# -46342_21-004_3_3.net
KiCad netlist of a schematic drawn in Altium Designer
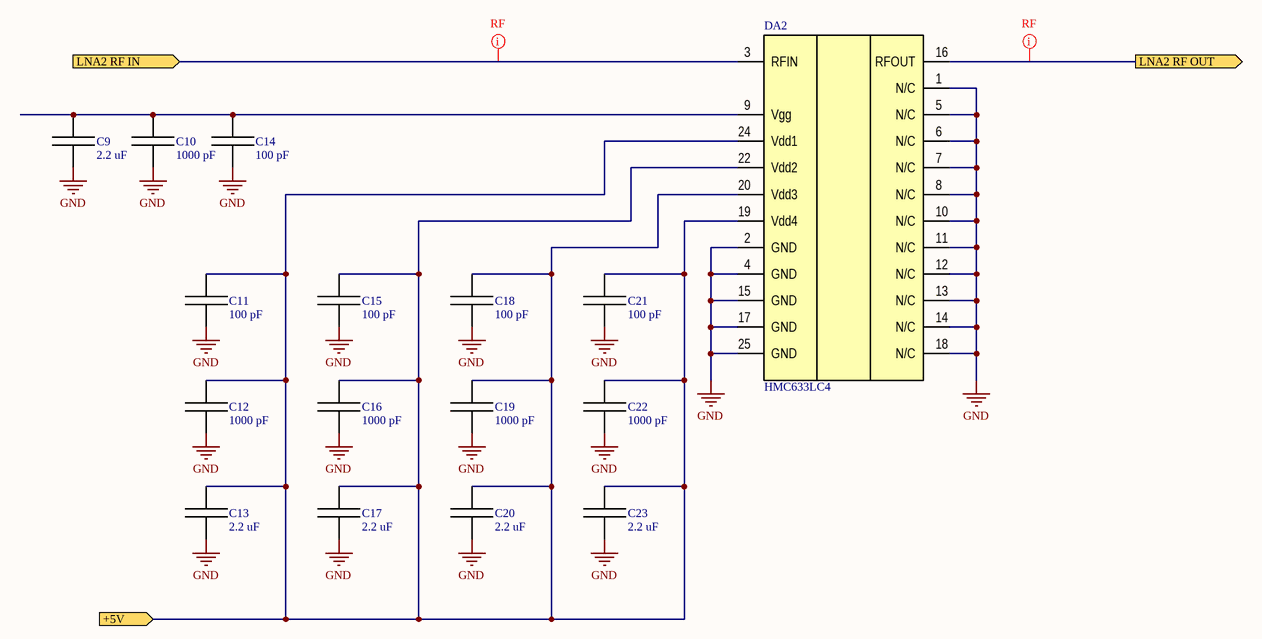
[diagram p0: МПСУ-46342.21-004 Э3 Лист3.SchDoc]

(export (version "E")
  (design (tool "Eeschema 10.0.6"))
  (components
    (comp (ref "C9")
      (value "2.2 uF")
      (footprint "CAPC100X50X55L20N")
      (description "Capacitor, generic")
      (fields (field (name "TOLERANCE") "5 %"))
      (libsource (lib "StudentsLibrary") (part "Capacitor"))
    )
    (comp (ref "C10")
      (value "1000 pF")
      (footprint "CAPC100X50X55L20N")
      (description "Capacitor, generic")
      (fields (field (name "TOLERANCE") "5 %"))
      (libsource (lib "StudentsLibrary") (part "Capacitor"))
    )
    (comp (ref "C11")
      (value "100 pF")
      (footprint "CAPC100X50X55L20N")
      (description "Capacitor, generic")
      (fields (field (name "TOLERANCE") "5 %"))
      (libsource (lib "StudentsLibrary") (part "Capacitor"))
    )
    (comp (ref "C12")
      (value "1000 pF")
      (footprint "CAPC100X50X55L20N")
      (description "Capacitor, generic")
      (fields (field (name "TOLERANCE") "5 %"))
      (libsource (lib "StudentsLibrary") (part "Capacitor"))
    )
    (comp (ref "C13")
      (value "2.2 uF")
      (footprint "CAPC160X80X90L30N")
      (description "Capacitor, generic")
      (fields (field (name "TOLERANCE") "5 %"))
      (libsource (lib "StudentsLibrary") (part "Capacitor"))
    )
    (comp (ref "C14")
      (value "100 pF")
      (footprint "CAPC100X50X55L20N")
      (description "Capacitor, generic")
      (fields (field (name "TOLERANCE") "5 %"))
      (libsource (lib "StudentsLibrary") (part "Capacitor"))
    )
    (comp (ref "C15")
      (value "100 pF")
      (footprint "CAPC100X50X55L20N")
      (description "Capacitor, generic")
      (fields (field (name "TOLERANCE") "5 %"))
      (libsource (lib "StudentsLibrary") (part "Capacitor"))
    )
    (comp (ref "C16")
      (value "1000 pF")
      (footprint "CAPC100X50X55L20N")
      (description "Capacitor, generic")
      (fields (field (name "TOLERANCE") "5 %"))
      (libsource (lib "StudentsLibrary") (part "Capacitor"))
    )
    (comp (ref "C17")
      (value "2.2 uF")
      (footprint "CAPC160X80X90L30N")
      (description "Capacitor, generic")
      (fields (field (name "TOLERANCE") "5 %"))
      (libsource (lib "StudentsLibrary") (part "Capacitor"))
    )
    (comp (ref "C18")
      (value "100 pF")
      (footprint "CAPC100X50X55L20N")
      (description "Capacitor, generic")
      (fields (field (name "TOLERANCE") "5 %"))
      (libsource (lib "StudentsLibrary") (part "Capacitor"))
    )
    (comp (ref "C19")
      (value "1000 pF")
      (footprint "CAPC100X50X55L20N")
      (description "Capacitor, generic")
      (fields (field (name "TOLERANCE") "5 %"))
      (libsource (lib "StudentsLibrary") (part "Capacitor"))
    )
    (comp (ref "C20")
      (value "2.2 uF")
      (footprint "CAPC160X80X90L30N")
      (description "Capacitor, generic")
      (fields (field (name "TOLERANCE") "5 %"))
      (libsource (lib "StudentsLibrary") (part "Capacitor"))
    )
    (comp (ref "C21")
      (value "100 pF")
      (footprint "CAPC100X50X55L20N")
      (description "Capacitor, generic")
      (fields (field (name "TOLERANCE") "5 %"))
      (libsource (lib "StudentsLibrary") (part "Capacitor"))
    )
    (comp (ref "C22")
      (value "1000 pF")
      (footprint "CAPC100X50X55L20N")
      (description "Capacitor, generic")
      (fields (field (name "TOLERANCE") "5 %"))
      (libsource (lib "StudentsLibrary") (part "Capacitor"))
    )
    (comp (ref "C23")
      (value "2.2 uF")
      (footprint "CAPC160X80X90L30N")
      (description "Capacitor, generic")
      (fields (field (name "TOLERANCE") "5 %"))
      (libsource (lib "StudentsLibrary") (part "Capacitor"))
    )
    (comp (ref "DA2")
      (value "HMC633LC4")
      (footprint "PQFN25P50_390X390X100L32X30T250N")
      (description "GaAs, pHEMT MMIC DRIVERAMPLIFIER, 5.5 - 17 GHz")
      (fields (field (name "MANUFACTURER") "Analog Devices"))
      (libsource (lib "receiver") (part "HMC633LC4"))
    )
  )
  (nets
    (net (code "1") (name "/+5V") (class "Default")
      (node (ref "C11") (pin "2") (pinfunction "2_2") (pintype "passive"))
      (node (ref "C12") (pin "2") (pinfunction "2_2") (pintype "passive"))
      (node (ref "C13") (pin "2") (pinfunction "2_2") (pintype "passive"))
      (node (ref "C15") (pin "2") (pinfunction "2_2") (pintype "passive"))
      (node (ref "C16") (pin "2") (pinfunction "2_2") (pintype "passive"))
      (node (ref "C17") (pin "2") (pinfunction "2_2") (pintype "passive"))
      (node (ref "C18") (pin "2") (pinfunction "2_2") (pintype "passive"))
      (node (ref "C19") (pin "2") (pinfunction "2_2") (pintype "passive"))
      (node (ref "C20") (pin "2") (pinfunction "2_2") (pintype "passive"))
      (node (ref "C21") (pin "2") (pinfunction "2_2") (pintype "passive"))
      (node (ref "C22") (pin "2") (pinfunction "2_2") (pintype "passive"))
      (node (ref "C23") (pin "2") (pinfunction "2_2") (pintype "passive"))
      (node (ref "DA2") (pin "19") (pinfunction "Vdd4_19") (pintype "passive"))
      (node (ref "DA2") (pin "20") (pinfunction "Vdd3_20") (pintype "passive"))
      (node (ref "DA2") (pin "22") (pinfunction "Vdd2_22") (pintype "passive"))
      (node (ref "DA2") (pin "24") (pinfunction "Vdd1_24") (pintype "passive"))
    )
    (net (code "2") (name "/LNA2 RF IN") (class "Default")
      (node (ref "DA2") (pin "3") (pinfunction "RFIN_3") (pintype "passive"))
    )
    (net (code "3") (name "/LNA2 RF OUT") (class "Default")
      (node (ref "DA2") (pin "16") (pinfunction "RFOUT_16") (pintype "passive"))
    )
    (net (code "4") (name "GND") (class "Default")
      (node (ref "C10") (pin "1") (pinfunction "1_1") (pintype "passive"))
      (node (ref "C11") (pin "1") (pinfunction "1_1") (pintype "passive"))
      (node (ref "C12") (pin "1") (pinfunction "1_1") (pintype "passive"))
      (node (ref "C13") (pin "1") (pinfunction "1_1") (pintype "passive"))
      (node (ref "C14") (pin "1") (pinfunction "1_1") (pintype "passive"))
      (node (ref "C15") (pin "1") (pinfunction "1_1") (pintype "passive"))
      (node (ref "C16") (pin "1") (pinfunction "1_1") (pintype "passive"))
      (node (ref "C17") (pin "1") (pinfunction "1_1") (pintype "passive"))
      (node (ref "C18") (pin "1") (pinfunction "1_1") (pintype "passive"))
      (node (ref "C19") (pin "1") (pinfunction "1_1") (pintype "passive"))
      (node (ref "C20") (pin "1") (pinfunction "1_1") (pintype "passive"))
      (node (ref "C21") (pin "1") (pinfunction "1_1") (pintype "passive"))
      (node (ref "C22") (pin "1") (pinfunction "1_1") (pintype "passive"))
      (node (ref "C23") (pin "1") (pinfunction "1_1") (pintype "passive"))
      (node (ref "C9") (pin "1") (pinfunction "1_1") (pintype "passive"))
      (node (ref "DA2") (pin "1") (pinfunction "N/C_1") (pintype "passive"))
      (node (ref "DA2") (pin "10") (pinfunction "N/C_10") (pintype "passive"))
      (node (ref "DA2") (pin "11") (pinfunction "N/C_11") (pintype "passive"))
      (node (ref "DA2") (pin "12") (pinfunction "N/C_12") (pintype "passive"))
      (node (ref "DA2") (pin "13") (pinfunction "N/C_13") (pintype "passive"))
      (node (ref "DA2") (pin "14") (pinfunction "N/C_14") (pintype "passive"))
      (node (ref "DA2") (pin "15") (pinfunction "GND_15") (pintype "passive"))
      (node (ref "DA2") (pin "17") (pinfunction "GND_17") (pintype "passive"))
      (node (ref "DA2") (pin "18") (pinfunction "N/C_18") (pintype "passive"))
      (node (ref "DA2") (pin "2") (pinfunction "GND_2") (pintype "passive"))
      (node (ref "DA2") (pin "25") (pinfunction "GND_25") (pintype "passive"))
      (node (ref "DA2") (pin "4") (pinfunction "GND_4") (pintype "passive"))
      (node (ref "DA2") (pin "5") (pinfunction "N/C_5") (pintype "passive"))
      (node (ref "DA2") (pin "6") (pinfunction "N/C_6") (pintype "passive"))
      (node (ref "DA2") (pin "7") (pinfunction "N/C_7") (pintype "passive"))
      (node (ref "DA2") (pin "8") (pinfunction "N/C_8") (pintype "passive"))
    )
    (net (code "5") (name "Net-(DA2-Vgg)") (class "Default")
      (node (ref "C10") (pin "2") (pinfunction "2_2") (pintype "passive"))
      (node (ref "C14") (pin "2") (pinfunction "2_2") (pintype "passive"))
      (node (ref "C9") (pin "2") (pinfunction "2_2") (pintype "passive"))
      (node (ref "DA2") (pin "9") (pinfunction "Vgg_9") (pintype "passive"))
    )
  )
)
